# hw_ESP8266_RFID_WinformC__DiemDanhSV.net
KiCad netlist of a schematic drawn in Altium Designer
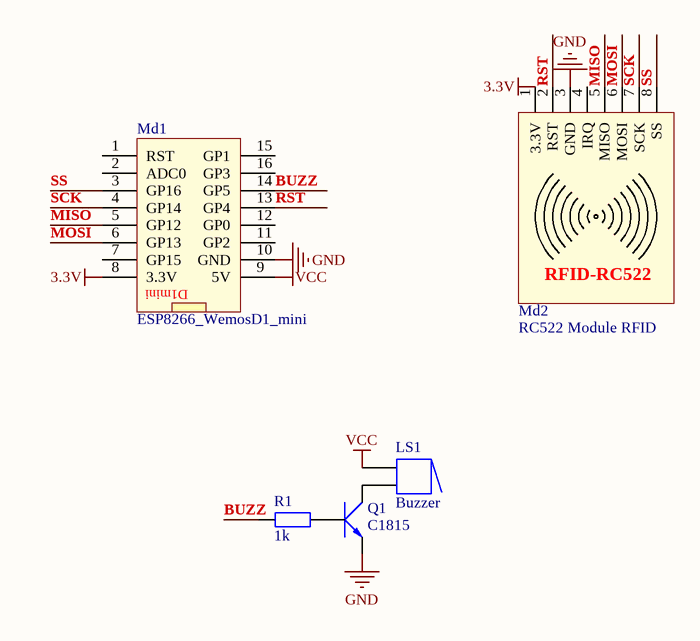
[diagram p0: hw_ESP8266_RFID_WinformC#_DiemDanhSV.SchDoc]

(export (version "E")
  (design (tool "Eeschema 10.0.6"))
  (components
    (comp (ref "LS1")
      (value "Buzzer")
      (footprint "Buzzer")
      (description "Magnetic Transducer Buzzer")
      (fields (field (name "PUBLISHER") "Altium Limited"))
      (libsource (lib "hphonglib") (part "Buzzer"))
    )
    (comp (ref "Md1")
      (value "ESP8266_WemosD1_mini")
      (footprint "ESP8266 WemosD1 mini")
      (libsource (lib "DaoTakIsaac") (part "ESP8266_WemosD1_mini"))
    )
    (comp (ref "Md2")
      (value "RC522 Module RFID")
      (footprint "RC522_Module")
      (libsource (lib "DaoTakIsaac") (part "RFID_RC522_Module"))
    )
    (comp (ref "Q1")
      (value "C1815")
      (footprint "QTO-92")
      (description "NPN 600mW, ECB")
      (libsource (lib "hphonglib") (part "C1815_1"))
    )
    (comp (ref "R1")
      (value "1k")
      (footprint "R1/4W")
      (description "Resistor 1/4W")
      (libsource (lib "hphonglib") (part "R1/4W"))
    )
  )
  (nets
    (net (code "1") (name "/BUZZ") (class "Default")
      (node (ref "Md1") (pin "14") (pinfunction "GP5_14") (pintype "passive"))
      (node (ref "R1") (pin "1") (pinfunction "1_1") (pintype "passive"))
    )
    (net (code "2") (name "/MISO") (class "Default")
      (node (ref "Md1") (pin "5") (pinfunction "GP12_5") (pintype "passive"))
      (node (ref "Md2") (pin "5") (pinfunction "MISO_5") (pintype "passive"))
    )
    (net (code "3") (name "/MOSI") (class "Default")
      (node (ref "Md1") (pin "6") (pinfunction "GP13_6") (pintype "passive"))
      (node (ref "Md2") (pin "6") (pinfunction "MOSI_6") (pintype "passive"))
    )
    (net (code "4") (name "/RST") (class "Default")
      (node (ref "Md1") (pin "13") (pinfunction "GP4_13") (pintype "passive"))
      (node (ref "Md2") (pin "2") (pinfunction "RST_2") (pintype "passive"))
    )
    (net (code "5") (name "/SCK") (class "Default")
      (node (ref "Md1") (pin "4") (pinfunction "GP14_4") (pintype "passive"))
      (node (ref "Md2") (pin "7") (pinfunction "SCK_7") (pintype "passive"))
    )
    (net (code "6") (name "/SS") (class "Default")
      (node (ref "Md1") (pin "3") (pinfunction "GP16_3") (pintype "passive"))
      (node (ref "Md2") (pin "8") (pinfunction "SS_8") (pintype "passive"))
    )
    (net (code "7") (name "3.3V") (class "Default")
      (node (ref "Md1") (pin "8") (pinfunction "3.3V_8") (pintype "passive"))
      (node (ref "Md2") (pin "1") (pinfunction "3.3V_1") (pintype "passive"))
    )
    (net (code "8") (name "GND") (class "Default")
      (node (ref "Md1") (pin "10") (pinfunction "GND_10") (pintype "passive"))
      (node (ref "Md2") (pin "3") (pinfunction "GND_3") (pintype "passive"))
      (node (ref "Q1") (pin "1") (pinfunction "E_1") (pintype "passive"))
    )
    (net (code "9") (name "Net-(Q1-B)") (class "Default")
      (node (ref "Q1") (pin "3") (pinfunction "B_3") (pintype "passive"))
      (node (ref "R1") (pin "2") (pinfunction "2_2") (pintype "passive"))
    )
    (net (code "10") (name "Net-(Q1-C)") (class "Default")
      (node (ref "LS1") (pin "2") (pinfunction "2_2") (pintype "passive"))
      (node (ref "Q1") (pin "2") (pinfunction "C_2") (pintype "passive"))
    )
    (net (code "11") (name "VCC") (class "Default")
      (node (ref "LS1") (pin "1") (pinfunction "1_1") (pintype "passive"))
      (node (ref "Md1") (pin "9") (pinfunction "5V_9") (pintype "passive"))
    )
    (net (code "12") (name "unconnected-(Md1-ADC0-Pad2)") (class "Default")
      (node (ref "Md1") (pin "2") (pinfunction "ADC0_2") (pintype "passive"))
    )
    (net (code "13") (name "unconnected-(Md1-GP0-Pad12)") (class "Default")
      (node (ref "Md1") (pin "12") (pinfunction "GP0_12") (pintype "passive"))
    )
    (net (code "14") (name "unconnected-(Md1-GP1-Pad15)") (class "Default")
      (node (ref "Md1") (pin "15") (pinfunction "GP1_15") (pintype "passive"))
    )
    (net (code "15") (name "unconnected-(Md1-GP2-Pad11)") (class "Default")
      (node (ref "Md1") (pin "11") (pinfunction "GP2_11") (pintype "passive"))
    )
    (net (code "16") (name "unconnected-(Md1-GP3-Pad16)") (class "Default")
      (node (ref "Md1") (pin "16") (pinfunction "GP3_16") (pintype "passive"))
    )
    (net (code "17") (name "unconnected-(Md1-GP15-Pad7)") (class "Default")
      (node (ref "Md1") (pin "7") (pinfunction "GP15_7") (pintype "passive"))
    )
    (net (code "18") (name "unconnected-(Md1-RST-Pad1)") (class "Default")
      (node (ref "Md1") (pin "1") (pinfunction "RST_1") (pintype "passive"))
    )
    (net (code "19") (name "unconnected-(Md2-IRQ-Pad4)") (class "Default")
      (node (ref "Md2") (pin "4") (pinfunction "IRQ_4") (pintype "passive"))
    )
  )
)
